# projek.net
KiCad netlist of a schematic drawn in EAGLE
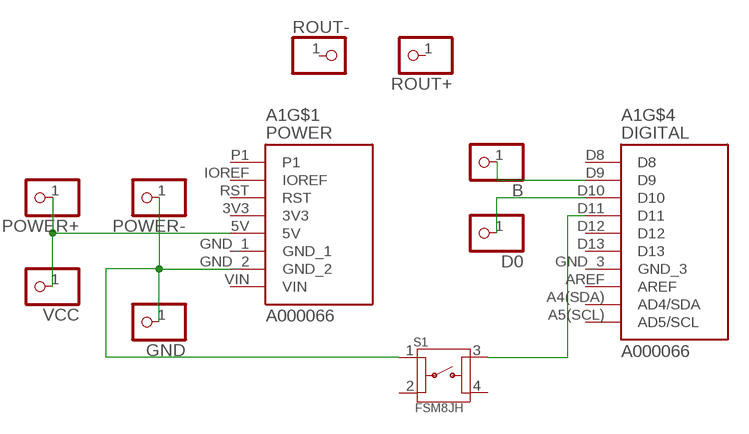
[diagram p0: schematic, sheet 1]

(export (version "E")
  (design (tool "Eeschema 10.0.6"))
  (components
    (comp (ref "A1")
      (value "A000066")
      (footprint "eagle-import:ARDUINO_A000066")
      (fields (field (name "MF") "Arduino") (field (name "MP") "ARDUINO UNO REV3"))
      (libsource (lib "eagle-import") (part "A000066"))
    )
    (comp (ref "B")
      (value "PINHD-1X1")
      (footprint "eagle-import:1X01")
      (libsource (lib "eagle-import") (part "PINHD-1X1"))
    )
    (comp (ref "D0")
      (value "PINHD-1X1")
      (footprint "eagle-import:1X01")
      (libsource (lib "eagle-import") (part "PINHD-1X1"))
    )
    (comp (ref "GND")
      (value "PINHD-1X1")
      (footprint "eagle-import:1X01")
      (libsource (lib "eagle-import") (part "PINHD-1X1"))
    )
    (comp (ref "POWER+")
      (value "PINHD-1X1")
      (footprint "eagle-import:1X01")
      (libsource (lib "eagle-import") (part "PINHD-1X1"))
    )
    (comp (ref "POWER-")
      (value "PINHD-1X1")
      (footprint "eagle-import:1X01")
      (libsource (lib "eagle-import") (part "PINHD-1X1"))
    )
    (comp (ref "ROUT+")
      (value "PINHD-1X1")
      (footprint "eagle-import:1X01")
      (libsource (lib "eagle-import") (part "PINHD-1X1"))
    )
    (comp (ref "ROUT-")
      (value "PINHD-1X1")
      (footprint "eagle-import:1X01")
      (libsource (lib "eagle-import") (part "PINHD-1X1"))
    )
    (comp (ref "S1")
      (value "FSM8JH")
      (footprint "eagle-import:SW_FSM8JH")
      (fields (field (name "MF") "TE Connectivity"))
      (libsource (lib "eagle-import") (part "FSM8JH"))
    )
    (comp (ref "VCC")
      (value "PINHD-1X1")
      (footprint "eagle-import:1X01")
      (libsource (lib "eagle-import") (part "PINHD-1X1"))
    )
  )
  (nets
    (net (code "1") (name "/3V3") (class "Default")
      (node (ref "A1") (pin "3V3") (pinfunction "3V3_3V3") (pintype "power_in"))
    )
    (net (code "2") (name "/GND_1") (class "Default")
      (node (ref "A1") (pin "GND_1") (pinfunction "GND_1_GND_1") (pintype "power_in"))
    )
    (net (code "3") (name "/GND_3") (class "Default")
      (node (ref "A1") (pin "GND_3") (pinfunction "GND_3_GND_3") (pintype "power_in"))
    )
    (net (code "4") (name "/VIN") (class "Default")
      (node (ref "A1") (pin "VIN") (pinfunction "VIN_VIN") (pintype "power_in"))
    )
    (net (code "5") (name "Net-(A1-Pad5V)") (class "Default")
      (node (ref "A1") (pin "5V") (pinfunction "5V_5V") (pintype "power_in"))
      (node (ref "POWER+") (pin "1") (pinfunction "1_1") (pintype "passive"))
      (node (ref "VCC") (pin "1") (pinfunction "1_1") (pintype "passive"))
    )
    (net (code "6") (name "Net-(A1-PadD9)") (class "Default")
      (node (ref "A1") (pin "D9") (pinfunction "D9_D9") (pintype "bidirectional"))
      (node (ref "B") (pin "1") (pinfunction "1_1") (pintype "passive"))
    )
    (net (code "7") (name "Net-(A1-PadD10)") (class "Default")
      (node (ref "A1") (pin "D10") (pinfunction "D10_D10") (pintype "bidirectional"))
      (node (ref "D0") (pin "1") (pinfunction "1_1") (pintype "passive"))
    )
    (net (code "8") (name "Net-(A1-PadD11)") (class "Default")
      (node (ref "A1") (pin "D11") (pinfunction "D11_D11") (pintype "bidirectional"))
      (node (ref "S1") (pin "3") (pinfunction "3_3") (pintype "passive"))
    )
    (net (code "9") (name "Net-(A1-PadGND_2)") (class "Default")
      (node (ref "A1") (pin "GND_2") (pinfunction "GND_2_GND_2") (pintype "power_in"))
      (node (ref "GND") (pin "1") (pinfunction "1_1") (pintype "passive"))
      (node (ref "POWER-") (pin "1") (pinfunction "1_1") (pintype "passive"))
      (node (ref "S1") (pin "1") (pinfunction "1_1") (pintype "passive"))
    )
    (net (code "10") (name "unconnected-(A1-PadAREF)") (class "Default")
      (node (ref "A1") (pin "AREF") (pinfunction "AREF_AREF") (pintype "bidirectional"))
    )
    (net (code "11") (name "unconnected-(A1-PadD8)") (class "Default")
      (node (ref "A1") (pin "D8") (pinfunction "D8_D8") (pintype "bidirectional"))
    )
    (net (code "12") (name "unconnected-(A1-PadD12)") (class "Default")
      (node (ref "A1") (pin "D12") (pinfunction "D12_D12") (pintype "bidirectional"))
    )
    (net (code "13") (name "unconnected-(A1-PadD13)") (class "Default")
      (node (ref "A1") (pin "D13") (pinfunction "D13_D13") (pintype "bidirectional"))
    )
    (net (code "14") (name "unconnected-(A1-PadIOREF)") (class "Default")
      (node (ref "A1") (pin "IOREF") (pinfunction "IOREF_IOREF") (pintype "bidirectional"))
    )
    (net (code "15") (name "unconnected-(A1-PadP1)") (class "Default")
      (node (ref "A1") (pin "P1") (pinfunction "P1_P1") (pintype "bidirectional"))
    )
    (net (code "16") (name "unconnected-(A1-PadRST)") (class "Default")
      (node (ref "A1") (pin "RST") (pinfunction "RST_RST") (pintype "bidirectional"))
    )
    (net (code "17") (name "unconnected-(A1D-AD4{slash}SDA-PadA4(SDA))") (class "Default")
      (node (ref "A1") (pin "A4(SDA)") (pinfunction "AD4/SDA_A4(SDA)") (pintype "bidirectional"))
    )
    (net (code "18") (name "unconnected-(A1D-AD5{slash}SCL-PadA5(SCL))") (class "Default")
      (node (ref "A1") (pin "A5(SCL)") (pinfunction "AD5/SCL_A5(SCL)") (pintype "bidirectional"))
    )
    (net (code "19") (name "unconnected-(ROUT+-Pad1)") (class "Default")
      (node (ref "ROUT+") (pin "1") (pinfunction "1_1") (pintype "passive"))
    )
    (net (code "20") (name "unconnected-(ROUT--Pad1)") (class "Default")
      (node (ref "ROUT-") (pin "1") (pinfunction "1_1") (pintype "passive"))
    )
    (net (code "21") (name "unconnected-(S1-Pad2)") (class "Default")
      (node (ref "S1") (pin "2") (pinfunction "2_2") (pintype "passive"))
    )
    (net (code "22") (name "unconnected-(S1-Pad4)") (class "Default")
      (node (ref "S1") (pin "4") (pinfunction "4_4") (pintype "passive"))
    )
  )
)
